# Sheet1.net
KiCad netlist of a schematic drawn in Altium Designer
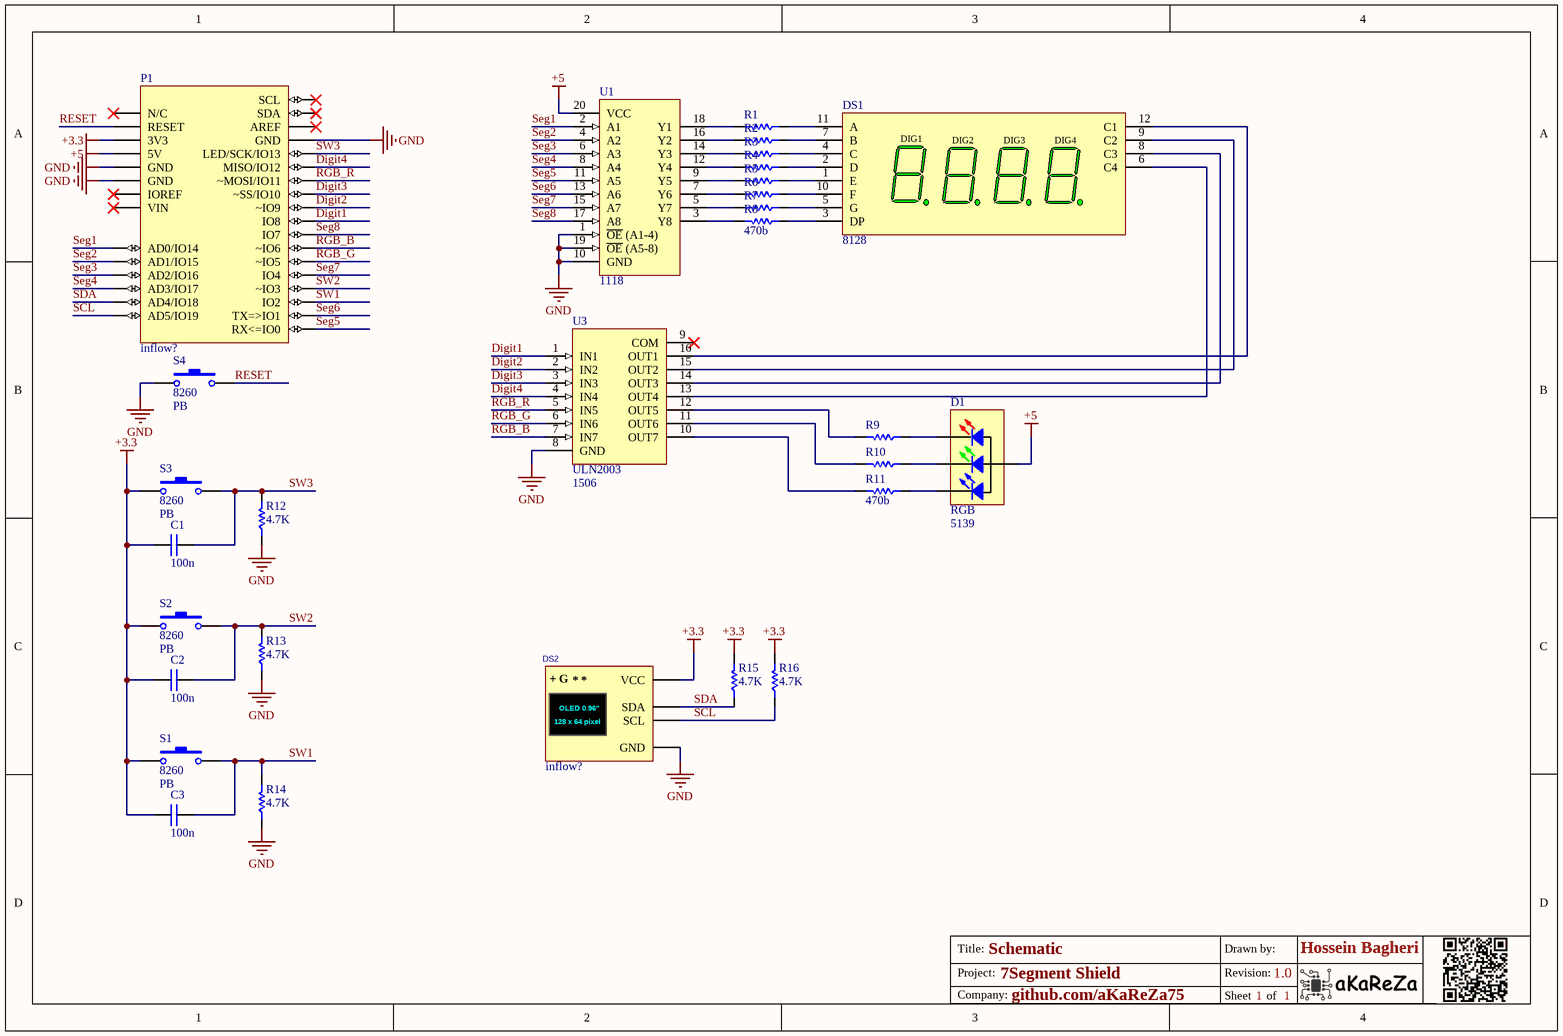
[diagram p0: Sheet1.SchDoc]

(export (version "E")
  (design (tool "Eeschema 10.0.6"))
  (components
    (comp (ref "C1")
      (value "100n")
      (footprint "Cap - 100nF")
      (description "Multi layer capacitor")
      (fields (field (name "VALIDATION") "Valid"))
      (libsource (lib "aKaReZa") (part "Cap_Multi_THT"))
    )
    (comp (ref "C2")
      (value "100n")
      (footprint "Cap - 100nF")
      (description "Multi layer capacitor")
      (fields (field (name "VALIDATION") "Valid"))
      (libsource (lib "aKaReZa") (part "Cap_Multi_THT"))
    )
    (comp (ref "C3")
      (value "100n")
      (footprint "Cap - 100nF")
      (description "Multi layer capacitor")
      (fields (field (name "VALIDATION") "Valid"))
      (libsource (lib "aKaReZa") (part "Cap_Multi_THT"))
    )
    (comp (ref "D1")
      (value "RGB")
      (footprint "RGB_DIP")
      (description "SMD 5050 LED RGB and Other")
      (fields (field (name "INFLOW") "5139") (field (name "VALIDATION") "Valid"))
      (libsource (lib "aKaReZa") (part "Semi_LED_RGB_THT"))
    )
    (comp (ref "DS1")
      (value "4Digit, Red")
      (footprint "7Seg-MPX4-30.2x14.1mm")
      (description "7Segment-MPX4-CC")
      (fields (field (name "INFLOW") "8128"))
      (libsource (lib "aKaReZa") (part "ModSen_7Seg_MPX4_CC"))
    )
    (comp (ref "DS2")
      (value "SSD1306")
      (footprint "OLED_SSD1306_64_I2C")
      (description "Oled Display")
      (fields (field (name "INFLOW") "inflow?") (field (name "VALIDATION") "Valid"))
      (libsource (lib "aKaReZa") (part "ModSen_LCD_Oled_0.96_2"))
    )
    (comp (ref "P1")
      (value "UNO")
      (footprint "Arduino_uno_S_3")
      (description "Arduino uno slave")
      (fields (field (name "INFLOW") "inflow?"))
      (libsource (lib "aKaReZa") (part "Con_Arduino_UNO_S"))
    )
    (comp (ref "R1")
      (value "470b")
      (footprint "RES 1206 (3216X08L)")
      (description "Resistor")
      (fields (field (name "VALIDATION") "Valid"))
      (libsource (lib "aKaReZa") (part "Res_SMD_1206"))
    )
    (comp (ref "R2")
      (value "470b")
      (footprint "RES 1206 (3216X08L)")
      (description "Resistor")
      (fields (field (name "VALIDATION") "Valid"))
      (libsource (lib "aKaReZa") (part "Res_SMD_1206"))
    )
    (comp (ref "R3")
      (value "470b")
      (footprint "RES 1206 (3216X08L)")
      (description "Resistor")
      (fields (field (name "VALIDATION") "Valid"))
      (libsource (lib "aKaReZa") (part "Res_SMD_1206"))
    )
    (comp (ref "R4")
      (value "470b")
      (footprint "RES 1206 (3216X08L)")
      (description "Resistor")
      (fields (field (name "VALIDATION") "Valid"))
      (libsource (lib "aKaReZa") (part "Res_SMD_1206"))
    )
    (comp (ref "R5")
      (value "470b")
      (footprint "RES 1206 (3216X08L)")
      (description "Resistor")
      (fields (field (name "VALIDATION") "Valid"))
      (libsource (lib "aKaReZa") (part "Res_SMD_1206"))
    )
    (comp (ref "R6")
      (value "470b")
      (footprint "RES 1206 (3216X08L)")
      (description "Resistor")
      (fields (field (name "VALIDATION") "Valid"))
      (libsource (lib "aKaReZa") (part "Res_SMD_1206"))
    )
    (comp (ref "R7")
      (value "470b")
      (footprint "RES 1206 (3216X08L)")
      (description "Resistor")
      (fields (field (name "VALIDATION") "Valid"))
      (libsource (lib "aKaReZa") (part "Res_SMD_1206"))
    )
    (comp (ref "R8")
      (value "470b")
      (footprint "RES 1206 (3216X08L)")
      (description "Resistor")
      (fields (field (name "VALIDATION") "Valid"))
      (libsource (lib "aKaReZa") (part "Res_SMD_1206"))
    )
    (comp (ref "R9")
      (value "470b")
      (footprint "RES 1206 (3216X08L)")
      (description "Resistor")
      (fields (field (name "VALIDATION") "Valid"))
      (libsource (lib "aKaReZa") (part "Res_SMD_1206"))
    )
    (comp (ref "R10")
      (value "470b")
      (footprint "RES 1206 (3216X08L)")
      (description "Resistor")
      (fields (field (name "VALIDATION") "Valid"))
      (libsource (lib "aKaReZa") (part "Res_SMD_1206"))
    )
    (comp (ref "R11")
      (value "470b")
      (footprint "RES 1206 (3216X08L)")
      (description "Resistor")
      (fields (field (name "VALIDATION") "Valid"))
      (libsource (lib "aKaReZa") (part "Res_SMD_1206"))
    )
    (comp (ref "R12")
      (value "4.7K")
      (footprint "RES 1206 (3216X08L)")
      (description "Resistor")
      (fields (field (name "VALIDATION") "Valid"))
      (libsource (lib "aKaReZa") (part "Res_SMD_1206"))
    )
    (comp (ref "R13")
      (value "4.7K")
      (footprint "RES 1206 (3216X08L)")
      (description "Resistor")
      (fields (field (name "VALIDATION") "Valid"))
      (libsource (lib "aKaReZa") (part "Res_SMD_1206"))
    )
    (comp (ref "R14")
      (value "4.7K")
      (footprint "RES 1206 (3216X08L)")
      (description "Resistor")
      (fields (field (name "VALIDATION") "Valid"))
      (libsource (lib "aKaReZa") (part "Res_SMD_1206"))
    )
    (comp (ref "R15")
      (value "4.7K")
      (footprint "RES 1206 (3216X08L)")
      (description "Resistor")
      (fields (field (name "VALIDATION") "Valid"))
      (libsource (lib "aKaReZa") (part "Res_SMD_1206"))
    )
    (comp (ref "R16")
      (value "4.7K")
      (footprint "RES 1206 (3216X08L)")
      (description "Resistor")
      (fields (field (name "VALIDATION") "Valid"))
      (libsource (lib "aKaReZa") (part "Res_SMD_1206"))
    )
    (comp (ref "S1")
      (value "PB")
      (footprint "SW_PB_SMD_2PIN_SPST_6X3X2")
      (description "SMT Tactile ‎Switch")
      (fields (field (name "INFLOW") "8260"))
      (libsource (lib "aKaReZa") (part "SW_PushButton_2_SMD"))
    )
    (comp (ref "S2")
      (value "PB")
      (footprint "SW_PB_SMD_2PIN_SPST_6X3X2")
      (description "SMT Tactile ‎Switch")
      (fields (field (name "INFLOW") "8260"))
      (libsource (lib "aKaReZa") (part "SW_PushButton_2_SMD"))
    )
    (comp (ref "S3")
      (value "PB")
      (footprint "SW_PB_SMD_2PIN_SPST_6X3X2")
      (description "SMT Tactile ‎Switch")
      (fields (field (name "INFLOW") "8260"))
      (libsource (lib "aKaReZa") (part "SW_PushButton_2_SMD"))
    )
    (comp (ref "S4")
      (value "PB")
      (footprint "SW_PB_SMD_2PIN_SPST_6X3X2")
      (description "SMT Tactile ‎Switch")
      (fields (field (name "INFLOW") "8260"))
      (libsource (lib "aKaReZa") (part "SW_PushButton_2_SMD"))
    )
    (comp (ref "U1")
      (value "74HCT244")
      (footprint "PDIP20")
      (description "Octal Bus Buffer with 3 State Outputs (Non Inverted)")
      (fields (field (name "INFLOW") "1118"))
      (libsource (lib "aKaReZa") (part "IC_Logic_74HCT244"))
    )
    (comp (ref "U3")
      (value "ULN2003")
      (footprint "CDIP16")
      (description "Seven darlington array drivers")
      (fields (field (name "INFLOW") "1506") (field (name "VALIDATION") "Valid"))
      (libsource (lib "aKaReZa") (part "IC_Driver_ULN2003"))
    )
  )
  (nets
    (net (code "1") (name "+3.3") (class "Default")
      (node (ref "C1") (pin "1") (pinfunction "1_1") (pintype "passive"))
      (node (ref "C2") (pin "1") (pinfunction "1_1") (pintype "passive"))
      (node (ref "C3") (pin "1") (pinfunction "1_1") (pintype "passive"))
      (node (ref "DS2") (pin "1") (pinfunction "VCC_1") (pintype "passive"))
      (node (ref "P1") (pin "4") (pinfunction "3V3_4") (pintype "power_in"))
      (node (ref "R15") (pin "2") (pinfunction "2_2") (pintype "passive"))
      (node (ref "R16") (pin "2") (pinfunction "2_2") (pintype "passive"))
      (node (ref "S1") (pin "1") (pinfunction "1_1") (pintype "passive"))
      (node (ref "S2") (pin "1") (pinfunction "1_1") (pintype "passive"))
      (node (ref "S3") (pin "1") (pinfunction "1_1") (pintype "passive"))
    )
    (net (code "2") (name "+5") (class "Default")
      (node (ref "D1") (pin "2") (pinfunction "CA_2") (pintype "passive"))
      (node (ref "P1") (pin "5") (pinfunction "5V_5") (pintype "power_in"))
      (node (ref "U1") (pin "20") (pinfunction "VCC_20") (pintype "power_in"))
    )
    (net (code "3") (name "/Digit1") (class "Default")
      (node (ref "P1") (pin "23") (pinfunction "IO8_23") (pintype "bidirectional"))
      (node (ref "U3") (pin "1") (pinfunction "IN1_1") (pintype "input"))
    )
    (net (code "4") (name "/Digit2") (class "Default")
      (node (ref "P1") (pin "24") (pinfunction "~IO9_24") (pintype "bidirectional"))
      (node (ref "U3") (pin "2") (pinfunction "IN2_2") (pintype "input"))
    )
    (net (code "5") (name "/Digit3") (class "Default")
      (node (ref "P1") (pin "25") (pinfunction "~SS/IO10_25") (pintype "bidirectional"))
      (node (ref "U3") (pin "3") (pinfunction "IN3_3") (pintype "input"))
    )
    (net (code "6") (name "/Digit4") (class "Default")
      (node (ref "P1") (pin "27") (pinfunction "MISO/IO12_27") (pintype "bidirectional"))
      (node (ref "U3") (pin "4") (pinfunction "IN4_4") (pintype "input"))
    )
    (net (code "7") (name "/RESET") (class "Default")
      (node (ref "P1") (pin "3") (pinfunction "RESET_3") (pintype "passive"))
      (node (ref "S4") (pin "2") (pinfunction "2_2") (pintype "passive"))
    )
    (net (code "8") (name "/RGB_B") (class "Default")
      (node (ref "P1") (pin "21") (pinfunction "~IO6_21") (pintype "bidirectional"))
      (node (ref "U3") (pin "7") (pinfunction "IN7_7") (pintype "input"))
    )
    (net (code "9") (name "/RGB_G") (class "Default")
      (node (ref "P1") (pin "20") (pinfunction "~IO5_20") (pintype "bidirectional"))
      (node (ref "U3") (pin "6") (pinfunction "IN6_6") (pintype "input"))
    )
    (net (code "10") (name "/RGB_R") (class "Default")
      (node (ref "P1") (pin "26") (pinfunction "~MOSI/IO11_26") (pintype "bidirectional"))
      (node (ref "U3") (pin "5") (pinfunction "IN5_5") (pintype "input"))
    )
    (net (code "11") (name "/SCL") (class "Default")
      (node (ref "DS2") (pin "3") (pinfunction "SCL_3") (pintype "passive"))
      (node (ref "P1") (pin "14") (pinfunction "AD5/IO19_14") (pintype "bidirectional"))
      (node (ref "R16") (pin "1") (pinfunction "1_1") (pintype "passive"))
    )
    (net (code "12") (name "/SDA") (class "Default")
      (node (ref "DS2") (pin "4") (pinfunction "SDA_4") (pintype "passive"))
      (node (ref "P1") (pin "13") (pinfunction "AD4/IO18_13") (pintype "bidirectional"))
      (node (ref "R15") (pin "1") (pinfunction "1_1") (pintype "passive"))
    )
    (net (code "13") (name "/SW1") (class "Default")
      (node (ref "C3") (pin "2") (pinfunction "2_2") (pintype "passive"))
      (node (ref "P1") (pin "17") (pinfunction "IO2_17") (pintype "bidirectional"))
      (node (ref "R14") (pin "2") (pinfunction "2_2") (pintype "passive"))
      (node (ref "S1") (pin "2") (pinfunction "2_2") (pintype "passive"))
    )
    (net (code "14") (name "/SW2") (class "Default")
      (node (ref "C2") (pin "2") (pinfunction "2_2") (pintype "passive"))
      (node (ref "P1") (pin "18") (pinfunction "~IO3_18") (pintype "bidirectional"))
      (node (ref "R13") (pin "2") (pinfunction "2_2") (pintype "passive"))
      (node (ref "S2") (pin "2") (pinfunction "2_2") (pintype "passive"))
    )
    (net (code "15") (name "/SW3") (class "Default")
      (node (ref "C1") (pin "2") (pinfunction "2_2") (pintype "passive"))
      (node (ref "P1") (pin "28") (pinfunction "LED/SCK/IO13_28") (pintype "bidirectional"))
      (node (ref "R12") (pin "2") (pinfunction "2_2") (pintype "passive"))
      (node (ref "S3") (pin "2") (pinfunction "2_2") (pintype "passive"))
    )
    (net (code "16") (name "/Seg1") (class "Default")
      (node (ref "P1") (pin "9") (pinfunction "AD0/IO14_9") (pintype "bidirectional"))
      (node (ref "U1") (pin "2") (pinfunction "A1_2") (pintype "input"))
    )
    (net (code "17") (name "/Seg2") (class "Default")
      (node (ref "P1") (pin "10") (pinfunction "AD1/IO15_10") (pintype "bidirectional"))
      (node (ref "U1") (pin "4") (pinfunction "A2_4") (pintype "input"))
    )
    (net (code "18") (name "/Seg3") (class "Default")
      (node (ref "P1") (pin "11") (pinfunction "AD2/IO16_11") (pintype "bidirectional"))
      (node (ref "U1") (pin "6") (pinfunction "A3_6") (pintype "input"))
    )
    (net (code "19") (name "/Seg4") (class "Default")
      (node (ref "P1") (pin "12") (pinfunction "AD3/IO17_12") (pintype "bidirectional"))
      (node (ref "U1") (pin "8") (pinfunction "A4_8") (pintype "input"))
    )
    (net (code "20") (name "/Seg5") (class "Default")
      (node (ref "P1") (pin "15") (pinfunction "RX<=IO0_15") (pintype "bidirectional"))
      (node (ref "U1") (pin "11") (pinfunction "A5_11") (pintype "input"))
    )
    (net (code "21") (name "/Seg6") (class "Default")
      (node (ref "P1") (pin "16") (pinfunction "TX=>IO1_16") (pintype "bidirectional"))
      (node (ref "U1") (pin "13") (pinfunction "A6_13") (pintype "input"))
    )
    (net (code "22") (name "/Seg7") (class "Default")
      (node (ref "P1") (pin "19") (pinfunction "IO4_19") (pintype "bidirectional"))
      (node (ref "U1") (pin "15") (pinfunction "A7_15") (pintype "input"))
    )
    (net (code "23") (name "/Seg8") (class "Default")
      (node (ref "P1") (pin "22") (pinfunction "IO7_22") (pintype "bidirectional"))
      (node (ref "U1") (pin "17") (pinfunction "A8_17") (pintype "input"))
    )
    (net (code "24") (name "GND") (class "Default")
      (node (ref "DS2") (pin "2") (pinfunction "GND_2") (pintype "passive"))
      (node (ref "P1") (pin "29") (pinfunction "GND_29") (pintype "power_in"))
      (node (ref "P1") (pin "6") (pinfunction "GND_6") (pintype "power_in"))
      (node (ref "P1") (pin "7") (pinfunction "GND_7") (pintype "power_in"))
      (node (ref "R12") (pin "1") (pinfunction "1_1") (pintype "passive"))
      (node (ref "R13") (pin "1") (pinfunction "1_1") (pintype "passive"))
      (node (ref "R14") (pin "1") (pinfunction "1_1") (pintype "passive"))
      (node (ref "S4") (pin "1") (pinfunction "1_1") (pintype "passive"))
      (node (ref "U1") (pin "1") (pinfunction "~{OE}_(A1-4)_1") (pintype "input"))
      (node (ref "U1") (pin "10") (pinfunction "GND_10") (pintype "power_in"))
      (node (ref "U1") (pin "19") (pinfunction "~{OE}_(A5-8)_19") (pintype "input"))
      (node (ref "U3") (pin "8") (pinfunction "GND_8") (pintype "power_in"))
    )
    (net (code "25") (name "Net-(D1-B)") (class "Default")
      (node (ref "D1") (pin "4") (pinfunction "B_4") (pintype "passive"))
      (node (ref "R11") (pin "1") (pinfunction "1_1") (pintype "passive"))
    )
    (net (code "26") (name "Net-(D1-G)") (class "Default")
      (node (ref "D1") (pin "3") (pinfunction "G_3") (pintype "passive"))
      (node (ref "R10") (pin "1") (pinfunction "1_1") (pintype "passive"))
    )
    (net (code "27") (name "Net-(D1-R)") (class "Default")
      (node (ref "D1") (pin "1") (pinfunction "R_1") (pintype "passive"))
      (node (ref "R9") (pin "1") (pinfunction "1_1") (pintype "passive"))
    )
    (net (code "28") (name "Net-(DS1-A)") (class "Default")
      (node (ref "DS1") (pin "11") (pinfunction "A_11") (pintype "passive"))
      (node (ref "R1") (pin "1") (pinfunction "1_1") (pintype "passive"))
    )
    (net (code "29") (name "Net-(DS1-B)") (class "Default")
      (node (ref "DS1") (pin "7") (pinfunction "B_7") (pintype "passive"))
      (node (ref "R2") (pin "1") (pinfunction "1_1") (pintype "passive"))
    )
    (net (code "30") (name "Net-(DS1-C)") (class "Default")
      (node (ref "DS1") (pin "4") (pinfunction "C_4") (pintype "passive"))
      (node (ref "R3") (pin "1") (pinfunction "1_1") (pintype "passive"))
    )
    (net (code "31") (name "Net-(DS1-C1)") (class "Default")
      (node (ref "DS1") (pin "12") (pinfunction "C1_12") (pintype "passive"))
      (node (ref "U3") (pin "16") (pinfunction "OUT1_16") (pintype "open_collector"))
    )
    (net (code "32") (name "Net-(DS1-C2)") (class "Default")
      (node (ref "DS1") (pin "9") (pinfunction "C2_9") (pintype "passive"))
      (node (ref "U3") (pin "15") (pinfunction "OUT2_15") (pintype "open_collector"))
    )
    (net (code "33") (name "Net-(DS1-C3)") (class "Default")
      (node (ref "DS1") (pin "8") (pinfunction "C3_8") (pintype "passive"))
      (node (ref "U3") (pin "14") (pinfunction "OUT3_14") (pintype "open_collector"))
    )
    (net (code "34") (name "Net-(DS1-C4)") (class "Default")
      (node (ref "DS1") (pin "6") (pinfunction "C4_6") (pintype "passive"))
      (node (ref "U3") (pin "13") (pinfunction "OUT4_13") (pintype "open_collector"))
    )
    (net (code "35") (name "Net-(DS1-D)") (class "Default")
      (node (ref "DS1") (pin "2") (pinfunction "D_2") (pintype "passive"))
      (node (ref "R4") (pin "1") (pinfunction "1_1") (pintype "passive"))
    )
    (net (code "36") (name "Net-(DS1-DP)") (class "Default")
      (node (ref "DS1") (pin "3") (pinfunction "DP_3") (pintype "passive"))
      (node (ref "R8") (pin "1") (pinfunction "1_1") (pintype "passive"))
    )
    (net (code "37") (name "Net-(DS1-E)") (class "Default")
      (node (ref "DS1") (pin "1") (pinfunction "E_1") (pintype "passive"))
      (node (ref "R5") (pin "1") (pinfunction "1_1") (pintype "passive"))
    )
    (net (code "38") (name "Net-(DS1-F)") (class "Default")
      (node (ref "DS1") (pin "10") (pinfunction "F_10") (pintype "passive"))
      (node (ref "R6") (pin "1") (pinfunction "1_1") (pintype "passive"))
    )
    (net (code "39") (name "Net-(DS1-G)") (class "Default")
      (node (ref "DS1") (pin "5") (pinfunction "G_5") (pintype "passive"))
      (node (ref "R7") (pin "1") (pinfunction "1_1") (pintype "passive"))
    )
    (net (code "40") (name "Net-(U1-Y1)") (class "Default")
      (node (ref "R1") (pin "2") (pinfunction "2_2") (pintype "passive"))
      (node (ref "U1") (pin "18") (pinfunction "Y1_18") (pintype "tri_state"))
    )
    (net (code "41") (name "Net-(U1-Y2)") (class "Default")
      (node (ref "R2") (pin "2") (pinfunction "2_2") (pintype "passive"))
      (node (ref "U1") (pin "16") (pinfunction "Y2_16") (pintype "tri_state"))
    )
    (net (code "42") (name "Net-(U1-Y3)") (class "Default")
      (node (ref "R3") (pin "2") (pinfunction "2_2") (pintype "passive"))
      (node (ref "U1") (pin "14") (pinfunction "Y3_14") (pintype "tri_state"))
    )
    (net (code "43") (name "Net-(U1-Y4)") (class "Default")
      (node (ref "R4") (pin "2") (pinfunction "2_2") (pintype "passive"))
      (node (ref "U1") (pin "12") (pinfunction "Y4_12") (pintype "tri_state"))
    )
    (net (code "44") (name "Net-(U1-Y5)") (class "Default")
      (node (ref "R5") (pin "2") (pinfunction "2_2") (pintype "passive"))
      (node (ref "U1") (pin "9") (pinfunction "Y5_9") (pintype "tri_state"))
    )
    (net (code "45") (name "Net-(U1-Y6)") (class "Default")
      (node (ref "R6") (pin "2") (pinfunction "2_2") (pintype "passive"))
      (node (ref "U1") (pin "7") (pinfunction "Y6_7") (pintype "tri_state"))
    )
    (net (code "46") (name "Net-(U1-Y7)") (class "Default")
      (node (ref "R7") (pin "2") (pinfunction "2_2") (pintype "passive"))
      (node (ref "U1") (pin "5") (pinfunction "Y7_5") (pintype "tri_state"))
    )
    (net (code "47") (name "Net-(U1-Y8)") (class "Default")
      (node (ref "R8") (pin "2") (pinfunction "2_2") (pintype "passive"))
      (node (ref "U1") (pin "3") (pinfunction "Y8_3") (pintype "tri_state"))
    )
    (net (code "48") (name "Net-(U3-OUT5)") (class "Default")
      (node (ref "R9") (pin "2") (pinfunction "2_2") (pintype "passive"))
      (node (ref "U3") (pin "12") (pinfunction "OUT5_12") (pintype "open_collector"))
    )
    (net (code "49") (name "Net-(U3-OUT6)") (class "Default")
      (node (ref "R10") (pin "2") (pinfunction "2_2") (pintype "passive"))
      (node (ref "U3") (pin "11") (pinfunction "OUT6_11") (pintype "open_collector"))
    )
    (net (code "50") (name "Net-(U3-OUT7)") (class "Default")
      (node (ref "R11") (pin "2") (pinfunction "2_2") (pintype "passive"))
      (node (ref "U3") (pin "10") (pinfunction "OUT7_10") (pintype "open_collector"))
    )
    (net (code "51") (name "unconnected-(P1-AREF-Pad30)") (class "Default")
      (node (ref "P1") (pin "30") (pinfunction "AREF_30") (pintype "passive+no_connect"))
    )
    (net (code "52") (name "unconnected-(P1-IOREF-Pad2)") (class "Default")
      (node (ref "P1") (pin "2") (pinfunction "IOREF_2") (pintype "power_in+no_connect"))
    )
    (net (code "53") (name "unconnected-(P1-N{slash}C-Pad1)") (class "Default")
      (node (ref "P1") (pin "1") (pinfunction "N/C_1") (pintype "passive+no_connect"))
    )
    (net (code "54") (name "unconnected-(P1-SCL-Pad32)") (class "Default")
      (node (ref "P1") (pin "32") (pinfunction "SCL_32") (pintype "bidirectional+no_connect"))
    )
    (net (code "55") (name "unconnected-(P1-SDA-Pad31)") (class "Default")
      (node (ref "P1") (pin "31") (pinfunction "SDA_31") (pintype "bidirectional+no_connect"))
    )
    (net (code "56") (name "unconnected-(P1-VIN-Pad8)") (class "Default")
      (node (ref "P1") (pin "8") (pinfunction "VIN_8") (pintype "power_in+no_connect"))
    )
    (net (code "57") (name "unconnected-(U3-COM-Pad9)") (class "Default")
      (node (ref "U3") (pin "9") (pinfunction "COM_9") (pintype "passive+no_connect"))
    )
  )
)
